# WS2811Controller_SMD.net
KiCad netlist of a schematic drawn in EAGLE
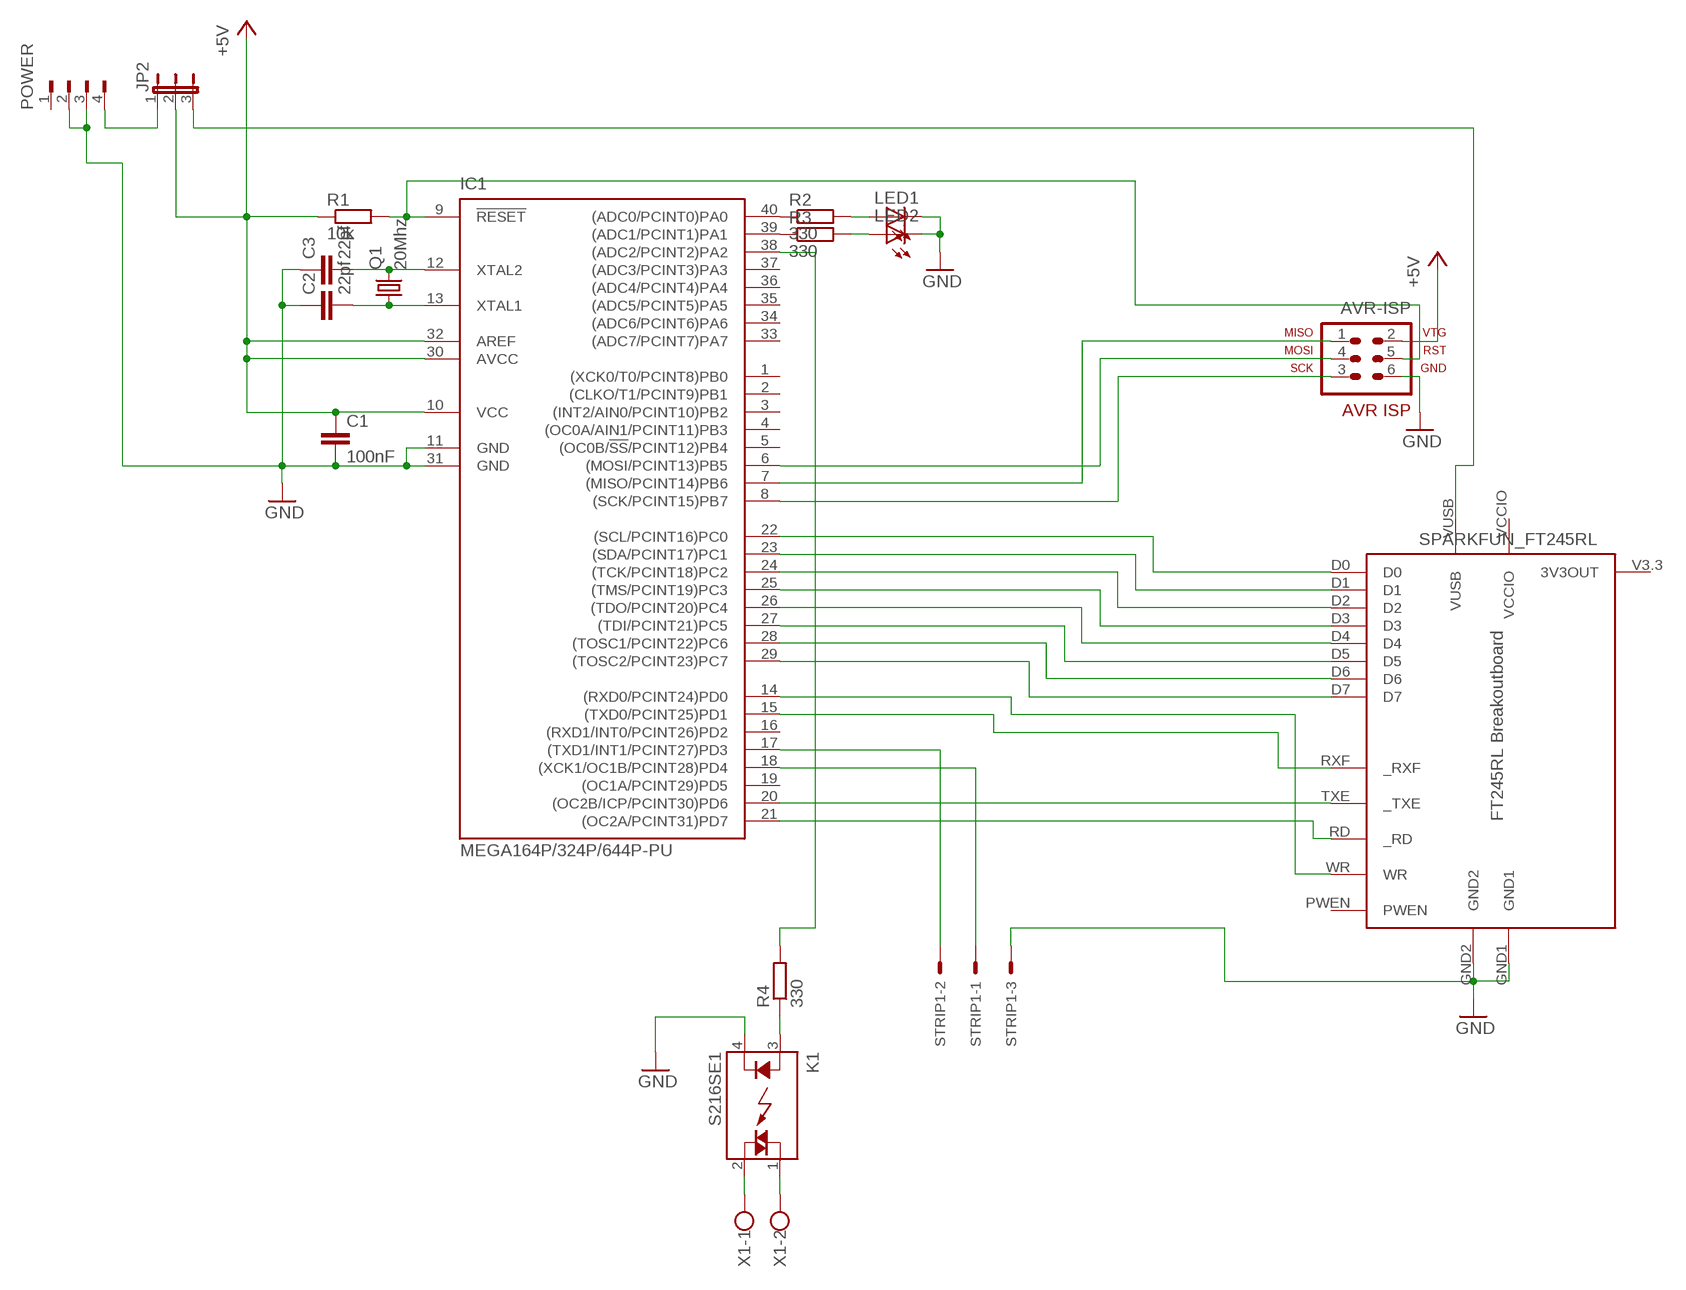
[diagram p0: schematic, sheet 1]

(export (version "E")
  (design (tool "Eeschema 10.0.6"))
  (components
    (comp (ref "AVR-ISP")
      (value "AVR-ISP-6")
      (footprint "eagle-import:AVR-ISP-6")
      (libsource (lib "eagle-import") (part "AVR-ISP-6"))
    )
    (comp (ref "C1")
      (value "100nF")
      (footprint "eagle-import:C050-030X075")
      (libsource (lib "eagle-import") (part "C-EU050-030X075"))
    )
    (comp (ref "C2")
      (value "22pf")
      (footprint "eagle-import:C050-024X044")
      (libsource (lib "eagle-import") (part "C-EU050-024X044"))
    )
    (comp (ref "C3")
      (value "22pf")
      (footprint "eagle-import:C050-024X044")
      (libsource (lib "eagle-import") (part "C-EU050-024X044"))
    )
    (comp (ref "IC1")
      (value "MEGA164P/324P/644P-PU")
      (footprint "eagle-import:DIL40")
      (libsource (lib "eagle-import") (part "MEGA164P/324P/644P-PU"))
    )
    (comp (ref "JP2")
      (value "JP2E")
      (footprint "eagle-import:JP2")
      (libsource (lib "eagle-import") (part "JP2E"))
    )
    (comp (ref "K1")
      (value "S216SE1")
      (footprint "eagle-import:S2XXEX")
      (libsource (lib "eagle-import") (part "S216SE1"))
    )
    (comp (ref "LED1")
      (value "LED3MM")
      (footprint "eagle-import:LED3MM")
      (libsource (lib "eagle-import") (part "LED3MM"))
    )
    (comp (ref "LED2")
      (value "LED3MM")
      (footprint "eagle-import:LED3MM")
      (libsource (lib "eagle-import") (part "LED3MM"))
    )
    (comp (ref "POWER")
      (value "FLOPPY-4")
      (footprint "eagle-import:FLOPPY-4")
      (libsource (lib "eagle-import") (part "FLOPPY-4"))
    )
    (comp (ref "Q1")
      (value "20Mhz")
      (footprint "eagle-import:HC49U70")
      (libsource (lib "eagle-import") (part "CRYSTALHC49U70"))
    )
    (comp (ref "R1")
      (value "10k")
      (footprint "eagle-import:0207_10")
      (libsource (lib "eagle-import") (part "R-EU_0207/10"))
    )
    (comp (ref "R2")
      (value "330")
      (footprint "eagle-import:0207_10")
      (libsource (lib "eagle-import") (part "R-EU_0207/10"))
    )
    (comp (ref "R3")
      (value "330")
      (footprint "eagle-import:0207_10")
      (libsource (lib "eagle-import") (part "R-EU_0207/10"))
    )
    (comp (ref "R4")
      (value "330")
      (footprint "eagle-import:0207_10")
      (libsource (lib "eagle-import") (part "R-EU_0207/10"))
    )
    (comp (ref "SPARKFUN_FT245RL")
      (value "FT245RL_BREAKOUTBOARD")
      (footprint "eagle-import:SPARKFUN_FT245RL_BOARD")
      (libsource (lib "eagle-import") (part "FT245RL_BREAKOUTBOARD"))
    )
    (comp (ref "STRIP1")
      (value "22-27-2031-03")
      (footprint "eagle-import:6410-03")
      (libsource (lib "eagle-import") (part "22-?-0327-2031"))
    )
    (comp (ref "X1")
      (value "W237-102")
      (footprint "eagle-import:W237-102")
      (fields (field (name "MPN") "237-102"))
      (libsource (lib "eagle-import") (part "W237-102"))
    )
  )
  (nets
    (net (code "1") (name "+5V") (class "Default")
      (node (ref "AVR-ISP") (pin "2") (pinfunction "2_2") (pintype "passive"))
      (node (ref "C1") (pin "1") (pinfunction "1_1") (pintype "passive"))
      (node (ref "IC1") (pin "10") (pinfunction "VCC_10") (pintype "power_in"))
      (node (ref "IC1") (pin "30") (pinfunction "AVCC_30") (pintype "power_in"))
      (node (ref "IC1") (pin "32") (pinfunction "AREF_32") (pintype "power_in"))
      (node (ref "JP2") (pin "2") (pinfunction "2_2") (pintype "passive"))
      (node (ref "R1") (pin "1") (pinfunction "1_1") (pintype "passive"))
    )
    (net (code "2") (name "/VCCIO") (class "Default")
      (node (ref "SPARKFUN_FT245RL") (pin "VCCIO") (pinfunction "VCCIO_VCCIO") (pintype "power_in"))
    )
    (net (code "3") (name "GND") (class "Default")
      (node (ref "AVR-ISP") (pin "6") (pinfunction "6_6") (pintype "passive"))
      (node (ref "C1") (pin "2") (pinfunction "2_2") (pintype "passive"))
      (node (ref "C2") (pin "1") (pinfunction "1_1") (pintype "passive"))
      (node (ref "C3") (pin "1") (pinfunction "1_1") (pintype "passive"))
      (node (ref "IC1") (pin "11") (pinfunction "GND_11") (pintype "power_in"))
      (node (ref "IC1") (pin "31") (pinfunction "GND_31") (pintype "power_in"))
      (node (ref "K1") (pin "4") (pinfunction "K_4") (pintype "passive"))
      (node (ref "LED1") (pin "K") (pinfunction "C_K") (pintype "passive"))
      (node (ref "LED2") (pin "K") (pinfunction "C_K") (pintype "passive"))
      (node (ref "POWER") (pin "2") (pinfunction "2_2") (pintype "passive"))
      (node (ref "POWER") (pin "3") (pinfunction "3_3") (pintype "passive"))
      (node (ref "SPARKFUN_FT245RL") (pin "GND1") (pinfunction "GND1_GND1") (pintype "power_in"))
      (node (ref "SPARKFUN_FT245RL") (pin "GND2") (pinfunction "GND2_GND2") (pintype "power_in"))
      (node (ref "STRIP1") (pin "3") (pinfunction "S_3") (pintype "passive"))
    )
    (net (code "4") (name "Net-(IC1-(ADC0{slash}PCINT0)PA0)") (class "Default")
      (node (ref "IC1") (pin "40") (pinfunction "(ADC0/PCINT0)PA0_40") (pintype "bidirectional"))
      (node (ref "R2") (pin "1") (pinfunction "1_1") (pintype "passive"))
    )
    (net (code "5") (name "Net-(IC1-(ADC1{slash}PCINT1)PA1)") (class "Default")
      (node (ref "IC1") (pin "39") (pinfunction "(ADC1/PCINT1)PA1_39") (pintype "bidirectional"))
      (node (ref "R3") (pin "1") (pinfunction "1_1") (pintype "passive"))
    )
    (net (code "6") (name "Net-(IC1-(ADC2{slash}PCINT2)PA2)") (class "Default")
      (node (ref "IC1") (pin "38") (pinfunction "(ADC2/PCINT2)PA2_38") (pintype "bidirectional"))
      (node (ref "R4") (pin "2") (pinfunction "2_2") (pintype "passive"))
    )
    (net (code "7") (name "Net-(IC1-(MISO{slash}PCINT14)PB6)") (class "Default")
      (node (ref "AVR-ISP") (pin "1") (pinfunction "1_1") (pintype "passive"))
      (node (ref "IC1") (pin "7") (pinfunction "(MISO/PCINT14)PB6_7") (pintype "bidirectional"))
    )
    (net (code "8") (name "Net-(IC1-(MOSI{slash}PCINT13)PB5)") (class "Default")
      (node (ref "AVR-ISP") (pin "4") (pinfunction "4_4") (pintype "passive"))
      (node (ref "IC1") (pin "6") (pinfunction "(MOSI/PCINT13)PB5_6") (pintype "bidirectional"))
    )
    (net (code "9") (name "Net-(IC1-(OC2A{slash}PCINT31)PD7)") (class "Default")
      (node (ref "IC1") (pin "21") (pinfunction "(OC2A/PCINT31)PD7_21") (pintype "bidirectional"))
      (node (ref "SPARKFUN_FT245RL") (pin "RD") (pinfunction "_RD_RD") (pintype "bidirectional"))
    )
    (net (code "10") (name "Net-(IC1-(OC2B{slash}ICP{slash}PCINT30)PD6)") (class "Default")
      (node (ref "IC1") (pin "20") (pinfunction "(OC2B/ICP/PCINT30)PD6_20") (pintype "bidirectional"))
      (node (ref "SPARKFUN_FT245RL") (pin "TXE") (pinfunction "_TXE_TXE") (pintype "bidirectional"))
    )
    (net (code "11") (name "Net-(IC1-(RXD0{slash}PCINT24)PD0)") (class "Default")
      (node (ref "IC1") (pin "14") (pinfunction "(RXD0/PCINT24)PD0_14") (pintype "bidirectional"))
      (node (ref "SPARKFUN_FT245RL") (pin "WR") (pinfunction "WR_WR") (pintype "bidirectional"))
    )
    (net (code "12") (name "Net-(IC1-(SCK{slash}PCINT15)PB7)") (class "Default")
      (node (ref "AVR-ISP") (pin "3") (pinfunction "3_3") (pintype "passive"))
      (node (ref "IC1") (pin "8") (pinfunction "(SCK/PCINT15)PB7_8") (pintype "bidirectional"))
    )
    (net (code "13") (name "Net-(IC1-(SCL{slash}PCINT16)PC0)") (class "Default")
      (node (ref "IC1") (pin "22") (pinfunction "(SCL/PCINT16)PC0_22") (pintype "bidirectional"))
      (node (ref "SPARKFUN_FT245RL") (pin "D0") (pinfunction "D0_D0") (pintype "output"))
    )
    (net (code "14") (name "Net-(IC1-(SDA{slash}PCINT17)PC1)") (class "Default")
      (node (ref "IC1") (pin "23") (pinfunction "(SDA/PCINT17)PC1_23") (pintype "bidirectional"))
      (node (ref "SPARKFUN_FT245RL") (pin "D1") (pinfunction "D1_D1") (pintype "input"))
    )
    (net (code "15") (name "Net-(IC1-(TCK{slash}PCINT18)PC2)") (class "Default")
      (node (ref "IC1") (pin "24") (pinfunction "(TCK/PCINT18)PC2_24") (pintype "bidirectional"))
      (node (ref "SPARKFUN_FT245RL") (pin "D2") (pinfunction "D2_D2") (pintype "output"))
    )
    (net (code "16") (name "Net-(IC1-(TDI{slash}PCINT21)PC5)") (class "Default")
      (node (ref "IC1") (pin "27") (pinfunction "(TDI/PCINT21)PC5_27") (pintype "bidirectional"))
      (node (ref "SPARKFUN_FT245RL") (pin "D5") (pinfunction "D5_D5") (pintype "input"))
    )
    (net (code "17") (name "Net-(IC1-(TDO{slash}PCINT20)PC4)") (class "Default")
      (node (ref "IC1") (pin "26") (pinfunction "(TDO/PCINT20)PC4_26") (pintype "bidirectional"))
      (node (ref "SPARKFUN_FT245RL") (pin "D4") (pinfunction "D4_D4") (pintype "output"))
    )
    (net (code "18") (name "Net-(IC1-(TMS{slash}PCINT19)PC3)") (class "Default")
      (node (ref "IC1") (pin "25") (pinfunction "(TMS/PCINT19)PC3_25") (pintype "bidirectional"))
      (node (ref "SPARKFUN_FT245RL") (pin "D3") (pinfunction "D3_D3") (pintype "input"))
    )
    (net (code "19") (name "Net-(IC1-(TOSC1{slash}PCINT22)PC6)") (class "Default")
      (node (ref "IC1") (pin "28") (pinfunction "(TOSC1/PCINT22)PC6_28") (pintype "bidirectional"))
      (node (ref "SPARKFUN_FT245RL") (pin "D6") (pinfunction "D6_D6") (pintype "input"))
    )
    (net (code "20") (name "Net-(IC1-(TOSC2{slash}PCINT23)PC7)") (class "Default")
      (node (ref "IC1") (pin "29") (pinfunction "(TOSC2/PCINT23)PC7_29") (pintype "bidirectional"))
      (node (ref "SPARKFUN_FT245RL") (pin "D7") (pinfunction "D7_D7") (pintype "input"))
    )
    (net (code "21") (name "Net-(IC1-(TXD0{slash}PCINT25)PD1)") (class "Default")
      (node (ref "IC1") (pin "15") (pinfunction "(TXD0/PCINT25)PD1_15") (pintype "bidirectional"))
      (node (ref "SPARKFUN_FT245RL") (pin "RXF") (pinfunction "_RXF_RXF") (pintype "bidirectional"))
    )
    (net (code "22") (name "Net-(IC1-(TXD1{slash}INT1{slash}PCINT27)PD3)") (class "Default")
      (node (ref "IC1") (pin "17") (pinfunction "(TXD1/INT1/PCINT27)PD3_17") (pintype "bidirectional"))
      (node (ref "STRIP1") (pin "2") (pinfunction "S_2") (pintype "passive"))
    )
    (net (code "23") (name "Net-(IC1-(XCK1{slash}OC1B{slash}PCINT28)PD4)") (class "Default")
      (node (ref "IC1") (pin "18") (pinfunction "(XCK1/OC1B/PCINT28)PD4_18") (pintype "bidirectional"))
      (node (ref "STRIP1") (pin "1") (pinfunction "S_1") (pintype "passive"))
    )
    (net (code "24") (name "Net-(IC1-XTAL1)") (class "Default")
      (node (ref "C2") (pin "2") (pinfunction "2_2") (pintype "passive"))
      (node (ref "IC1") (pin "13") (pinfunction "XTAL1_13") (pintype "input"))
      (node (ref "Q1") (pin "1") (pinfunction "1_1") (pintype "passive"))
    )
    (net (code "25") (name "Net-(IC1-XTAL2)") (class "Default")
      (node (ref "C3") (pin "2") (pinfunction "2_2") (pintype "passive"))
      (node (ref "IC1") (pin "12") (pinfunction "XTAL2_12") (pintype "output"))
      (node (ref "Q1") (pin "2") (pinfunction "2_2") (pintype "passive"))
    )
    (net (code "26") (name "Net-(IC1-~{RESET})") (class "Default")
      (node (ref "AVR-ISP") (pin "5") (pinfunction "5_5") (pintype "passive"))
      (node (ref "IC1") (pin "9") (pinfunction "~{RESET}_9") (pintype "input"))
      (node (ref "R1") (pin "2") (pinfunction "2_2") (pintype "passive"))
    )
    (net (code "27") (name "Net-(JP2-Pad1)") (class "Default")
      (node (ref "JP2") (pin "1") (pinfunction "1_1") (pintype "passive"))
      (node (ref "POWER") (pin "4") (pinfunction "4_4") (pintype "passive"))
    )
    (net (code "28") (name "Net-(JP2-Pad3)") (class "Default")
      (node (ref "JP2") (pin "3") (pinfunction "3_3") (pintype "passive"))
      (node (ref "SPARKFUN_FT245RL") (pin "VUSB") (pinfunction "VUSB_VUSB") (pintype "bidirectional"))
    )
    (net (code "29") (name "Net-(K1-A)") (class "Default")
      (node (ref "K1") (pin "3") (pinfunction "A_3") (pintype "passive"))
      (node (ref "R4") (pin "1") (pinfunction "1_1") (pintype "passive"))
    )
    (net (code "30") (name "Net-(K1-DS1)") (class "Default")
      (node (ref "K1") (pin "1") (pinfunction "DS1_1") (pintype "passive"))
      (node (ref "X1") (pin "2") (pinfunction "KL_2") (pintype "passive"))
    )
    (net (code "31") (name "Net-(K1-DS2)") (class "Default")
      (node (ref "K1") (pin "2") (pinfunction "DS2_2") (pintype "passive"))
      (node (ref "X1") (pin "1") (pinfunction "KL_1") (pintype "passive"))
    )
    (net (code "32") (name "Net-(LED1-PadA)") (class "Default")
      (node (ref "LED1") (pin "A") (pinfunction "A_A") (pintype "passive"))
      (node (ref "R2") (pin "2") (pinfunction "2_2") (pintype "passive"))
    )
    (net (code "33") (name "Net-(LED2-PadA)") (class "Default")
      (node (ref "LED2") (pin "A") (pinfunction "A_A") (pintype "passive"))
      (node (ref "R3") (pin "2") (pinfunction "2_2") (pintype "passive"))
    )
    (net (code "34") (name "unconnected-(IC1-(ADC3{slash}PCINT3)PA3-Pad37)") (class "Default")
      (node (ref "IC1") (pin "37") (pinfunction "(ADC3/PCINT3)PA3_37") (pintype "bidirectional"))
    )
    (net (code "35") (name "unconnected-(IC1-(ADC4{slash}PCINT4)PA4-Pad36)") (class "Default")
      (node (ref "IC1") (pin "36") (pinfunction "(ADC4/PCINT4)PA4_36") (pintype "bidirectional"))
    )
    (net (code "36") (name "unconnected-(IC1-(ADC5{slash}PCINT5)PA5-Pad35)") (class "Default")
      (node (ref "IC1") (pin "35") (pinfunction "(ADC5/PCINT5)PA5_35") (pintype "bidirectional"))
    )
    (net (code "37") (name "unconnected-(IC1-(ADC6{slash}PCINT6)PA6-Pad34)") (class "Default")
      (node (ref "IC1") (pin "34") (pinfunction "(ADC6/PCINT6)PA6_34") (pintype "bidirectional"))
    )
    (net (code "38") (name "unconnected-(IC1-(ADC7{slash}PCINT7)PA7-Pad33)") (class "Default")
      (node (ref "IC1") (pin "33") (pinfunction "(ADC7/PCINT7)PA7_33") (pintype "bidirectional"))
    )
    (net (code "39") (name "unconnected-(IC1-(CLKO{slash}T1{slash}PCINT9)PB1-Pad2)") (class "Default")
      (node (ref "IC1") (pin "2") (pinfunction "(CLKO/T1/PCINT9)PB1_2") (pintype "bidirectional"))
    )
    (net (code "40") (name "unconnected-(IC1-(INT2{slash}AIN0{slash}PCINT10)PB2-Pad3)") (class "Default")
      (node (ref "IC1") (pin "3") (pinfunction "(INT2/AIN0/PCINT10)PB2_3") (pintype "bidirectional"))
    )
    (net (code "41") (name "unconnected-(IC1-(OC0A{slash}AIN1{slash}PCINT11)PB3-Pad4)") (class "Default")
      (node (ref "IC1") (pin "4") (pinfunction "(OC0A/AIN1/PCINT11)PB3_4") (pintype "bidirectional"))
    )
    (net (code "42") (name "unconnected-(IC1-(OC0B{slash}~{SS}{slash}PCINT12)PB4-Pad5)") (class "Default")
      (node (ref "IC1") (pin "5") (pinfunction "(OC0B/~{SS}/PCINT12)PB4_5") (pintype "bidirectional"))
    )
    (net (code "43") (name "unconnected-(IC1-(OC1A{slash}PCINT29)PD5-Pad19)") (class "Default")
      (node (ref "IC1") (pin "19") (pinfunction "(OC1A/PCINT29)PD5_19") (pintype "bidirectional"))
    )
    (net (code "44") (name "unconnected-(IC1-(RXD1{slash}INT0{slash}PCINT26)PD2-Pad16)") (class "Default")
      (node (ref "IC1") (pin "16") (pinfunction "(RXD1/INT0/PCINT26)PD2_16") (pintype "bidirectional"))
    )
    (net (code "45") (name "unconnected-(IC1-(XCK0{slash}T0{slash}PCINT8)PB0-Pad1)") (class "Default")
      (node (ref "IC1") (pin "1") (pinfunction "(XCK0/T0/PCINT8)PB0_1") (pintype "bidirectional"))
    )
    (net (code "46") (name "unconnected-(POWER-Pad1)") (class "Default")
      (node (ref "POWER") (pin "1") (pinfunction "1_1") (pintype "passive"))
    )
    (net (code "47") (name "unconnected-(SPARKFUN_FT245RL-3V3OUT-PadV3.3)") (class "Default")
      (node (ref "SPARKFUN_FT245RL") (pin "V3.3") (pinfunction "3V3OUT_V3.3") (pintype "output"))
    )
    (net (code "48") (name "unconnected-(SPARKFUN_FT245RL-PadPWEN)") (class "Default")
      (node (ref "SPARKFUN_FT245RL") (pin "PWEN") (pinfunction "PWEN_PWEN") (pintype "bidirectional"))
    )
  )
)
